# config-bank3.net
KiCad netlist of a schematic drawn in Altium Designer
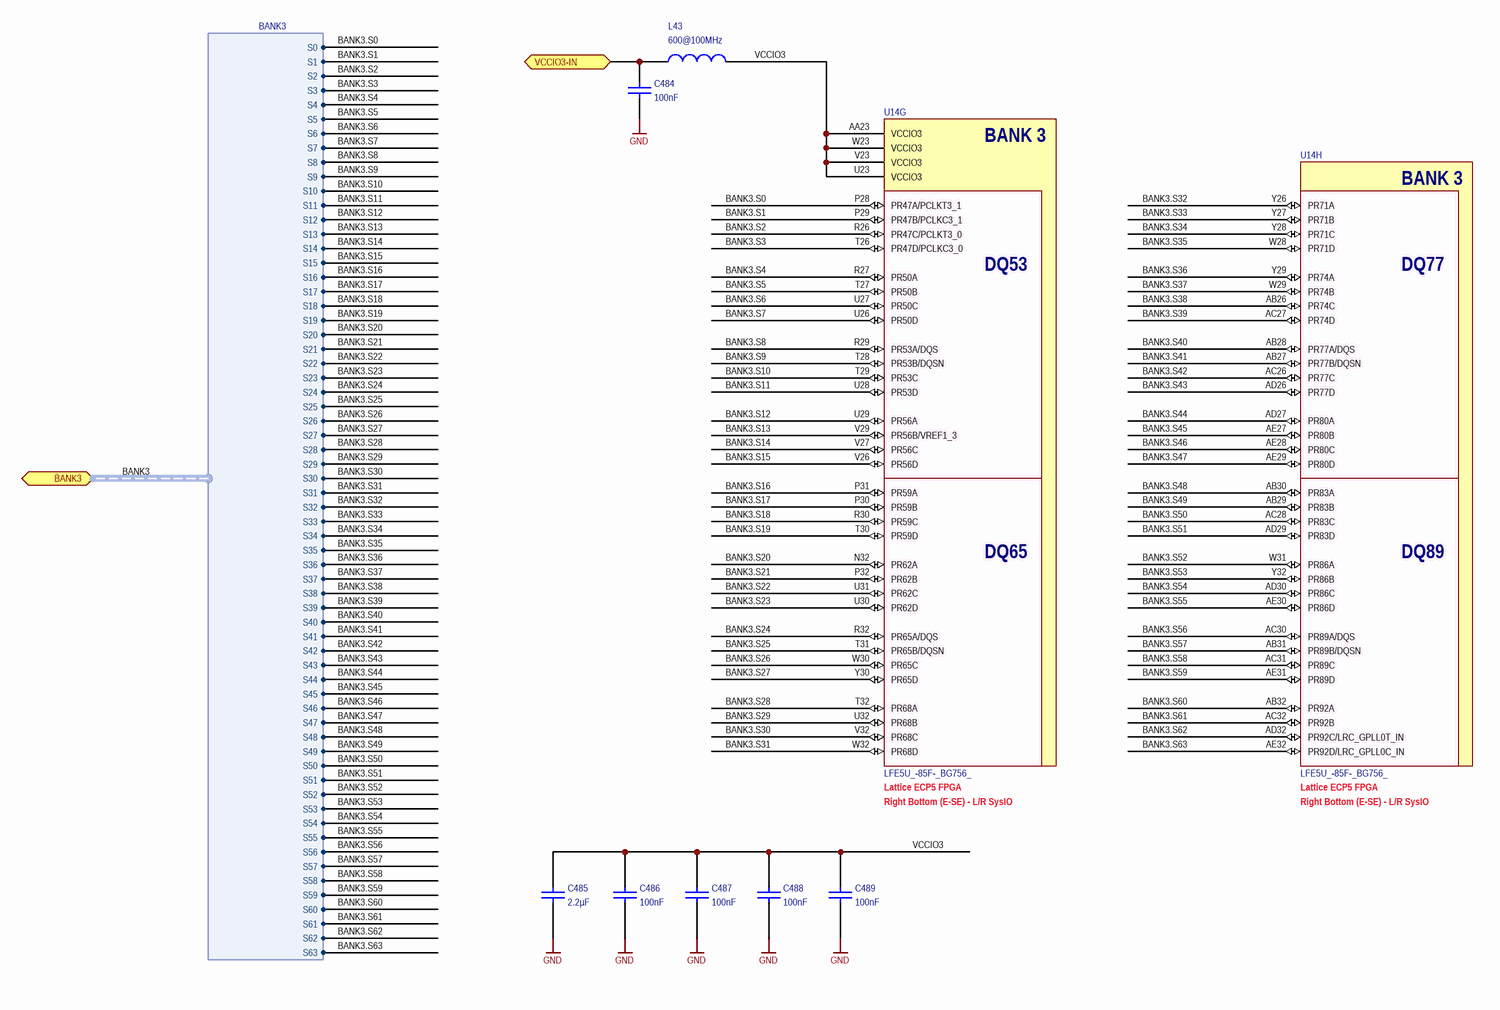
[diagram p0: config-bank3.SchDoc]

(export (version "E")
  (design (tool "Eeschema 10.0.6"))
  (components
    (comp (ref "C484")
      (value "100nF")
      (footprint "generic:CAPC1005X56N")
      (description "Ceramic Capacitor 100nF ±10% 16V X7R 0402")
      (fields (field (name "MANUFACTURER") "Murata") (field (name "TOLERANCE") "±10%"))
      (libsource (lib "murata") (part "GRM155R71A104KA01J"))
    )
    (comp (ref "C485")
      (value "2.2µF")
      (footprint "generic:CAPC1608X90N")
      (description "Ceramic Capacitor 2.2uF ±10% 10V X7R 0603")
      (fields (field (name "MANUFACTURER") "Murata") (field (name "TOLERANCE") "±10%"))
      (libsource (lib "murata") (part "GRM188R71A225KE15D"))
    )
    (comp (ref "C486")
      (value "100nF")
      (footprint "generic:CAPC1005X56N")
      (description "Ceramic Capacitor 100nF ±10% 16V X7R 0402")
      (fields (field (name "MANUFACTURER") "Murata") (field (name "TOLERANCE") "±10%"))
      (libsource (lib "murata") (part "GRM155R71A104KA01J"))
    )
    (comp (ref "C487")
      (value "100nF")
      (footprint "generic:CAPC1005X56N")
      (description "Ceramic Capacitor 100nF ±10% 16V X7R 0402")
      (fields (field (name "MANUFACTURER") "Murata") (field (name "TOLERANCE") "±10%"))
      (libsource (lib "murata") (part "GRM155R71A104KA01J"))
    )
    (comp (ref "C488")
      (value "100nF")
      (footprint "generic:CAPC1005X56N")
      (description "Ceramic Capacitor 100nF ±10% 16V X7R 0402")
      (fields (field (name "MANUFACTURER") "Murata") (field (name "TOLERANCE") "±10%"))
      (libsource (lib "murata") (part "GRM155R71A104KA01J"))
    )
    (comp (ref "C489")
      (value "100nF")
      (footprint "generic:CAPC1005X56N")
      (description "Ceramic Capacitor 100nF ±10% 16V X7R 0402")
      (fields (field (name "MANUFACTURER") "Murata") (field (name "TOLERANCE") "±10%"))
      (libsource (lib "murata") (part "GRM155R71A104KA01J"))
    )
    (comp (ref "L43")
      (value "600@100MHz")
      (footprint "0402")
      (description "Ferrite Bead 600-Ohm @ 100MHz 900mA 0402")
      (fields (field (name "MANUFACTURER") "Murata") (field (name "TOLERANCE") "±25%"))
      (libsource (lib "Graviton") (part "IND 0402"))
    )
    (comp (ref "U14")
      (value "LFE5U_-85F-_BG756_")
      (footprint "lattice:caBGA756")
      (description "ECP5 FPGA, 85k LUT, 756-caBGA")
      (fields (field (name "MANUFACTURER") "Lattice Semiconductor"))
      (libsource (lib "lattice") (part "LFE5U_-85F-_BG756_"))
    )
  )
  (nets
    (net (code "2") (name "/BANK3.S0") (class "Default")
      (node (ref "U14") (pin "P28") (pinfunction "PR47A/PCLKT3_1_P28") (pintype "bidirectional"))
    )
    (net (code "3") (name "/BANK3.S1") (class "Default")
      (node (ref "U14") (pin "P29") (pinfunction "PR47B/PCLKC3_1_P29") (pintype "bidirectional"))
    )
    (net (code "4") (name "/BANK3.S2") (class "Default")
      (node (ref "U14") (pin "R26") (pinfunction "PR47C/PCLKT3_0_R26") (pintype "bidirectional"))
    )
    (net (code "5") (name "/BANK3.S3") (class "Default")
      (node (ref "U14") (pin "T26") (pinfunction "PR47D/PCLKC3_0_T26") (pintype "bidirectional"))
    )
    (net (code "6") (name "/BANK3.S4") (class "Default")
      (node (ref "U14") (pin "R27") (pinfunction "PR50A_R27") (pintype "bidirectional"))
    )
    (net (code "7") (name "/BANK3.S5") (class "Default")
      (node (ref "U14") (pin "T27") (pinfunction "PR50B_T27") (pintype "bidirectional"))
    )
    (net (code "8") (name "/BANK3.S6") (class "Default")
      (node (ref "U14") (pin "U27") (pinfunction "PR50C_U27") (pintype "bidirectional"))
    )
    (net (code "9") (name "/BANK3.S7") (class "Default")
      (node (ref "U14") (pin "U26") (pinfunction "PR50D_U26") (pintype "bidirectional"))
    )
    (net (code "10") (name "/BANK3.S8") (class "Default")
      (node (ref "U14") (pin "R29") (pinfunction "PR53A/DQS_R29") (pintype "bidirectional"))
    )
    (net (code "11") (name "/BANK3.S9") (class "Default")
      (node (ref "U14") (pin "T28") (pinfunction "PR53B/DQSN_T28") (pintype "bidirectional"))
    )
    (net (code "12") (name "/BANK3.S10") (class "Default")
      (node (ref "U14") (pin "T29") (pinfunction "PR53C_T29") (pintype "bidirectional"))
    )
    (net (code "13") (name "/BANK3.S11") (class "Default")
      (node (ref "U14") (pin "U28") (pinfunction "PR53D_U28") (pintype "bidirectional"))
    )
    (net (code "14") (name "/BANK3.S12") (class "Default")
      (node (ref "U14") (pin "U29") (pinfunction "PR56A_U29") (pintype "bidirectional"))
    )
    (net (code "15") (name "/BANK3.S13") (class "Default")
      (node (ref "U14") (pin "V29") (pinfunction "PR56B/VREF1_3_V29") (pintype "bidirectional"))
    )
    (net (code "16") (name "/BANK3.S14") (class "Default")
      (node (ref "U14") (pin "V27") (pinfunction "PR56C_V27") (pintype "bidirectional"))
    )
    (net (code "17") (name "/BANK3.S15") (class "Default")
      (node (ref "U14") (pin "V26") (pinfunction "PR56D_V26") (pintype "bidirectional"))
    )
    (net (code "18") (name "/BANK3.S16") (class "Default")
      (node (ref "U14") (pin "P31") (pinfunction "PR59A_P31") (pintype "bidirectional"))
    )
    (net (code "19") (name "/BANK3.S17") (class "Default")
      (node (ref "U14") (pin "P30") (pinfunction "PR59B_P30") (pintype "bidirectional"))
    )
    (net (code "20") (name "/BANK3.S18") (class "Default")
      (node (ref "U14") (pin "R30") (pinfunction "PR59C_R30") (pintype "bidirectional"))
    )
    (net (code "21") (name "/BANK3.S19") (class "Default")
      (node (ref "U14") (pin "T30") (pinfunction "PR59D_T30") (pintype "bidirectional"))
    )
    (net (code "22") (name "/BANK3.S20") (class "Default")
      (node (ref "U14") (pin "N32") (pinfunction "PR62A_N32") (pintype "bidirectional"))
    )
    (net (code "23") (name "/BANK3.S21") (class "Default")
      (node (ref "U14") (pin "P32") (pinfunction "PR62B_P32") (pintype "bidirectional"))
    )
    (net (code "24") (name "/BANK3.S22") (class "Default")
      (node (ref "U14") (pin "U31") (pinfunction "PR62C_U31") (pintype "bidirectional"))
    )
    (net (code "25") (name "/BANK3.S23") (class "Default")
      (node (ref "U14") (pin "U30") (pinfunction "PR62D_U30") (pintype "bidirectional"))
    )
    (net (code "26") (name "/BANK3.S24") (class "Default")
      (node (ref "U14") (pin "R32") (pinfunction "PR65A/DQS_R32") (pintype "bidirectional"))
    )
    (net (code "27") (name "/BANK3.S25") (class "Default")
      (node (ref "U14") (pin "T31") (pinfunction "PR65B/DQSN_T31") (pintype "bidirectional"))
    )
    (net (code "28") (name "/BANK3.S26") (class "Default")
      (node (ref "U14") (pin "W30") (pinfunction "PR65C_W30") (pintype "bidirectional"))
    )
    (net (code "29") (name "/BANK3.S27") (class "Default")
      (node (ref "U14") (pin "Y30") (pinfunction "PR65D_Y30") (pintype "bidirectional"))
    )
    (net (code "30") (name "/BANK3.S28") (class "Default")
      (node (ref "U14") (pin "T32") (pinfunction "PR68A_T32") (pintype "bidirectional"))
    )
    (net (code "31") (name "/BANK3.S29") (class "Default")
      (node (ref "U14") (pin "U32") (pinfunction "PR68B_U32") (pintype "bidirectional"))
    )
    (net (code "32") (name "/BANK3.S30") (class "Default")
      (node (ref "U14") (pin "V32") (pinfunction "PR68C_V32") (pintype "bidirectional"))
    )
    (net (code "33") (name "/BANK3.S31") (class "Default")
      (node (ref "U14") (pin "W32") (pinfunction "PR68D_W32") (pintype "bidirectional"))
    )
    (net (code "34") (name "/BANK3.S32") (class "Default")
      (node (ref "U14") (pin "Y26") (pinfunction "PR71A_Y26") (pintype "bidirectional"))
    )
    (net (code "35") (name "/BANK3.S33") (class "Default")
      (node (ref "U14") (pin "Y27") (pinfunction "PR71B_Y27") (pintype "bidirectional"))
    )
    (net (code "36") (name "/BANK3.S34") (class "Default")
      (node (ref "U14") (pin "Y28") (pinfunction "PR71C_Y28") (pintype "bidirectional"))
    )
    (net (code "37") (name "/BANK3.S35") (class "Default")
      (node (ref "U14") (pin "W28") (pinfunction "PR71D_W28") (pintype "bidirectional"))
    )
    (net (code "38") (name "/BANK3.S36") (class "Default")
      (node (ref "U14") (pin "Y29") (pinfunction "PR74A_Y29") (pintype "bidirectional"))
    )
    (net (code "39") (name "/BANK3.S37") (class "Default")
      (node (ref "U14") (pin "W29") (pinfunction "PR74B_W29") (pintype "bidirectional"))
    )
    (net (code "40") (name "/BANK3.S38") (class "Default")
      (node (ref "U14") (pin "AB26") (pinfunction "PR74C_AB26") (pintype "bidirectional"))
    )
    (net (code "41") (name "/BANK3.S39") (class "Default")
      (node (ref "U14") (pin "AC27") (pinfunction "PR74D_AC27") (pintype "bidirectional"))
    )
    (net (code "42") (name "/BANK3.S40") (class "Default")
      (node (ref "U14") (pin "AB28") (pinfunction "PR77A/DQS_AB28") (pintype "bidirectional"))
    )
    (net (code "43") (name "/BANK3.S41") (class "Default")
      (node (ref "U14") (pin "AB27") (pinfunction "PR77B/DQSN_AB27") (pintype "bidirectional"))
    )
    (net (code "44") (name "/BANK3.S42") (class "Default")
      (node (ref "U14") (pin "AC26") (pinfunction "PR77C_AC26") (pintype "bidirectional"))
    )
    (net (code "45") (name "/BANK3.S43") (class "Default")
      (node (ref "U14") (pin "AD26") (pinfunction "PR77D_AD26") (pintype "bidirectional"))
    )
    (net (code "46") (name "/BANK3.S44") (class "Default")
      (node (ref "U14") (pin "AD27") (pinfunction "PR80A_AD27") (pintype "bidirectional"))
    )
    (net (code "47") (name "/BANK3.S45") (class "Default")
      (node (ref "U14") (pin "AE27") (pinfunction "PR80B_AE27") (pintype "bidirectional"))
    )
    (net (code "48") (name "/BANK3.S46") (class "Default")
      (node (ref "U14") (pin "AE28") (pinfunction "PR80C_AE28") (pintype "bidirectional"))
    )
    (net (code "49") (name "/BANK3.S47") (class "Default")
      (node (ref "U14") (pin "AE29") (pinfunction "PR80D_AE29") (pintype "bidirectional"))
    )
    (net (code "50") (name "/BANK3.S48") (class "Default")
      (node (ref "U14") (pin "AB30") (pinfunction "PR83A_AB30") (pintype "bidirectional"))
    )
    (net (code "51") (name "/BANK3.S49") (class "Default")
      (node (ref "U14") (pin "AB29") (pinfunction "PR83B_AB29") (pintype "bidirectional"))
    )
    (net (code "52") (name "/BANK3.S50") (class "Default")
      (node (ref "U14") (pin "AC28") (pinfunction "PR83C_AC28") (pintype "bidirectional"))
    )
    (net (code "53") (name "/BANK3.S51") (class "Default")
      (node (ref "U14") (pin "AD29") (pinfunction "PR83D_AD29") (pintype "bidirectional"))
    )
    (net (code "54") (name "/BANK3.S52") (class "Default")
      (node (ref "U14") (pin "W31") (pinfunction "PR86A_W31") (pintype "bidirectional"))
    )
    (net (code "55") (name "/BANK3.S53") (class "Default")
      (node (ref "U14") (pin "Y32") (pinfunction "PR86B_Y32") (pintype "bidirectional"))
    )
    (net (code "56") (name "/BANK3.S54") (class "Default")
      (node (ref "U14") (pin "AD30") (pinfunction "PR86C_AD30") (pintype "bidirectional"))
    )
    (net (code "57") (name "/BANK3.S55") (class "Default")
      (node (ref "U14") (pin "AE30") (pinfunction "PR86D_AE30") (pintype "bidirectional"))
    )
    (net (code "58") (name "/BANK3.S56") (class "Default")
      (node (ref "U14") (pin "AC30") (pinfunction "PR89A/DQS_AC30") (pintype "bidirectional"))
    )
    (net (code "59") (name "/BANK3.S57") (class "Default")
      (node (ref "U14") (pin "AB31") (pinfunction "PR89B/DQSN_AB31") (pintype "bidirectional"))
    )
    (net (code "60") (name "/BANK3.S58") (class "Default")
      (node (ref "U14") (pin "AC31") (pinfunction "PR89C_AC31") (pintype "bidirectional"))
    )
    (net (code "61") (name "/BANK3.S59") (class "Default")
      (node (ref "U14") (pin "AE31") (pinfunction "PR89D_AE31") (pintype "bidirectional"))
    )
    (net (code "62") (name "/BANK3.S60") (class "Default")
      (node (ref "U14") (pin "AB32") (pinfunction "PR92A_AB32") (pintype "bidirectional"))
    )
    (net (code "63") (name "/BANK3.S61") (class "Default")
      (node (ref "U14") (pin "AC32") (pinfunction "PR92B_AC32") (pintype "bidirectional"))
    )
    (net (code "64") (name "/BANK3.S62") (class "Default")
      (node (ref "U14") (pin "AD32") (pinfunction "PR92C/LRC_GPLL0T_IN_AD32") (pintype "bidirectional"))
    )
    (net (code "65") (name "/BANK3.S63") (class "Default")
      (node (ref "U14") (pin "AE32") (pinfunction "PR92D/LRC_GPLL0C_IN_AE32") (pintype "bidirectional"))
    )
    (net (code "67") (name "/VCCIO3") (class "Default")
      (node (ref "C485") (pin "2") (pinfunction "2_2") (pintype "passive"))
      (node (ref "C486") (pin "2") (pinfunction "2_2") (pintype "passive"))
      (node (ref "C487") (pin "2") (pinfunction "2_2") (pintype "passive"))
      (node (ref "C488") (pin "2") (pinfunction "2_2") (pintype "passive"))
      (node (ref "C489") (pin "2") (pinfunction "2_2") (pintype "passive"))
      (node (ref "L43") (pin "1") (pinfunction "1_1") (pintype "passive"))
      (node (ref "U14") (pin "AA23") (pinfunction "VCCIO3_AA23") (pintype "power_in"))
      (node (ref "U14") (pin "U23") (pinfunction "VCCIO3_U23") (pintype "power_in"))
      (node (ref "U14") (pin "V23") (pinfunction "VCCIO3_V23") (pintype "power_in"))
      (node (ref "U14") (pin "W23") (pinfunction "VCCIO3_W23") (pintype "power_in"))
    )
    (net (code "68") (name "/VCCIO3-IN") (class "Default")
      (node (ref "C484") (pin "2") (pinfunction "2_2") (pintype "passive"))
      (node (ref "L43") (pin "2") (pinfunction "2_2") (pintype "passive"))
    )
    (net (code "69") (name "GND") (class "Default")
      (node (ref "C484") (pin "1") (pinfunction "1_1") (pintype "passive"))
      (node (ref "C485") (pin "1") (pinfunction "1_1") (pintype "passive"))
      (node (ref "C486") (pin "1") (pinfunction "1_1") (pintype "passive"))
      (node (ref "C487") (pin "1") (pinfunction "1_1") (pintype "passive"))
      (node (ref "C488") (pin "1") (pinfunction "1_1") (pintype "passive"))
      (node (ref "C489") (pin "1") (pinfunction "1_1") (pintype "passive"))
    )
  )
)
